# GSM_Status_LED_Driver.net
KiCad netlist of a schematic drawn in Altium Designer
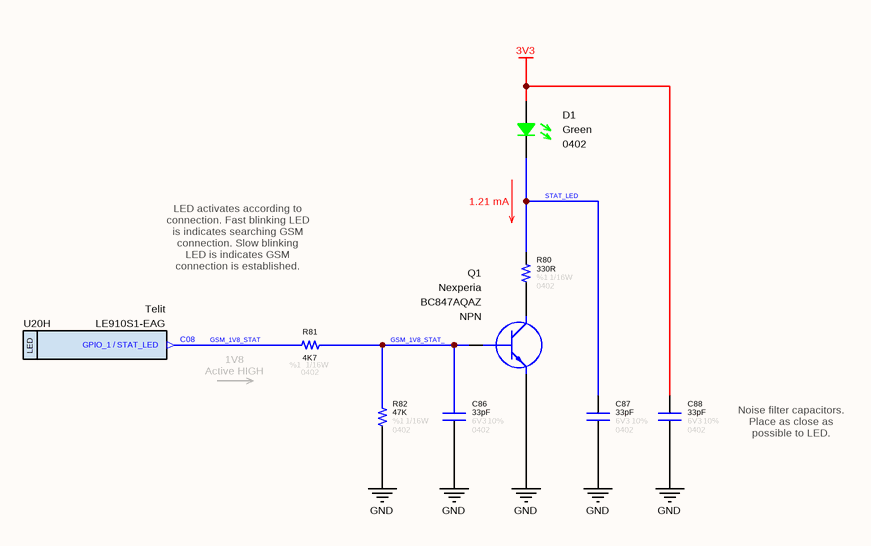
[diagram p0: GSM Status LED Driver.SchDoc]

(export (version "E")
  (design (tool "Eeschema 10.0.6"))
  (components
    (comp (ref "C86")
      (value "33pF")
      (footprint "CAPACITOR_0402")
      (description "Capacitor - 33pF [0402] (Ceramic)")
      (fields
        (field (name "MANUFACTURER PART NUMBER") "C0402C330J9RACAUTO")
        (field (name "TOLERANCE") "10%")
        (field (name "CASE") "0402")
        (field (name "VOLTAGE") "6V3")
      )
      (libsource (lib "Akkoyun") (part "Capacitor - 33pF [0402-6V3]"))
    )
    (comp (ref "C87")
      (value "33pF")
      (footprint "CAPACITOR_0402")
      (description "Capacitor - 33pF [0402] (Ceramic)")
      (fields
        (field (name "MANUFACTURER PART NUMBER") "C0402C330J9RACAUTO")
        (field (name "TOLERANCE") "10%")
        (field (name "CASE") "0402")
        (field (name "VOLTAGE") "6V3")
      )
      (libsource (lib "Akkoyun") (part "Capacitor - 33pF [0402-6V3]"))
    )
    (comp (ref "C88")
      (value "33pF")
      (footprint "CAPACITOR_0402")
      (description "Capacitor - 33pF [0402] (Ceramic)")
      (fields
        (field (name "MANUFACTURER PART NUMBER") "C0402C330J9RACAUTO")
        (field (name "TOLERANCE") "10%")
        (field (name "CASE") "0402")
        (field (name "VOLTAGE") "6V3")
      )
      (libsource (lib "Akkoyun") (part "Capacitor - 33pF [0402-6V3]"))
    )
    (comp (ref "D1")
      (value "SMD LED (Green)")
      (footprint "LED_0402")
      (description "Standard LEDs - SMD MINI-MOLD ULTRA COMPACT GREEN")
      (fields
        (field (name "MANUFACTURER PART NUMBER") "SML-P12MTT86R")
        (field (name "CASE") "0402")
        (field (name "COLOR") "Green")
      )
      (libsource (lib "Akkoyun") (part "Diode - LED (0402-Green)"))
    )
    (comp (ref "Q1")
      (value "BC847AQAZ")
      (footprint "SOT1215")
      (description "Bipolar NPN Transistors")
      (fields
        (field (name "MANUFACTURER NAME") "Nexperia")
        (field (name "MANUFACTURER PART NUMBER") "BC847AQAZ")
        (field (name "POLARITY") "NPN")
      )
      (libsource (lib "Akkoyun") (part "Transistor - BC847"))
    )
    (comp (ref "R80")
      (value "330R")
      (footprint "RESISTOR_0402")
      (description "Thick Film Resistors - SMD 1/16 W 330 Ohm 1%")
      (fields
        (field (name "MANUFACTURER PART NUMBER") "CRCW0402330RFKED")
        (field (name "CASE") "0402")
        (field (name "TOLERANCE") "%1")
        (field (name "POWER") "1/16W")
        (field (name "Comment") "330R - 0402 - %1 - 1/16W")
      )
      (libsource (lib "Akkoyun") (part "Resistor - 330R [0402]"))
    )
    (comp (ref "R81")
      (value "4K7")
      (footprint "RESISTOR_0402")
      (description "Thick Film Resistors - SMD 1/16 W 4.7 KOhm 1%")
      (fields
        (field (name "MANUFACTURER PART NUMBER") "CRCW04024K70FKED")
        (field (name "TOLERANCE") "%1")
        (field (name "CASE") "0402")
        (field (name "POWER") "1/16W")
        (field (name "Comment") "4K7 - 0402 - %1 - 1/16W")
      )
      (libsource (lib "Akkoyun") (part "Resistor - 4K7 [0402]"))
    )
    (comp (ref "R82")
      (value "47K")
      (footprint "RESISTOR_0402")
      (description "Thick Film Resistors - SMD 1/16 W 47 KOhm 1%")
      (fields
        (field (name "MANUFACTURER PART NUMBER") "CRCW040247K0FKED")
        (field (name "TOLERANCE") "%1")
        (field (name "CASE") "0402")
        (field (name "POWER") "1/16W")
        (field (name "Comment") "47K - 0402 - %1 - 1/16W")
      )
      (libsource (lib "Akkoyun") (part "Resistor - 47K [0402]"))
    )
    (comp (ref "U20")
      (value "LE910S1-EAG LTE GSM Module")
      (footprint "LE910 GSM Modem")
      (description "Telit LE910S1-EAG GPRS/GNSS Module")
      (fields
        (field (name "MANUFACTURER PART NUMBER") "LE910S1-EAG")
        (field (name "MANUFACTURER NAME") "Telit")
      )
      (libsource (lib "Akkoyun") (part "IC - LE910S1-EAG"))
    )
  )
  (nets
    (net (code "1") (name "/GSM_1V8_STAT") (class "Default")
      (node (ref "R81") (pin "2") (pinfunction "2_2") (pintype "passive"))
      (node (ref "U20") (pin "C08") (pinfunction "GPIO_1_/_STAT_LED_C08") (pintype "output"))
    )
    (net (code "2") (name "/GSM_1V8_STAT_") (class "Default")
      (node (ref "C86") (pin "2") (pinfunction "2_2") (pintype "passive"))
      (node (ref "Q1") (pin "1") (pinfunction "B_1") (pintype "passive"))
      (node (ref "R81") (pin "1") (pinfunction "1_1") (pintype "passive"))
      (node (ref "R82") (pin "2") (pinfunction "2_2") (pintype "passive"))
    )
    (net (code "3") (name "/STAT_LED") (class "Default")
      (node (ref "C87") (pin "2") (pinfunction "2_2") (pintype "passive"))
      (node (ref "D1") (pin "1") (pinfunction "1_1") (pintype "passive"))
      (node (ref "R80") (pin "2") (pinfunction "2_2") (pintype "passive"))
    )
    (net (code "4") (name "3V3") (class "Default")
      (node (ref "C88") (pin "2") (pinfunction "2_2") (pintype "passive"))
      (node (ref "D1") (pin "2") (pinfunction "2_2") (pintype "passive"))
    )
    (net (code "5") (name "GND") (class "Default")
      (node (ref "C86") (pin "1") (pinfunction "1_1") (pintype "passive"))
      (node (ref "C87") (pin "1") (pinfunction "1_1") (pintype "passive"))
      (node (ref "C88") (pin "1") (pinfunction "1_1") (pintype "passive"))
      (node (ref "Q1") (pin "2") (pinfunction "E_2") (pintype "passive"))
      (node (ref "R82") (pin "1") (pinfunction "1_1") (pintype "passive"))
    )
    (net (code "6") (name "Net-(Q1-C)") (class "Default")
      (node (ref "Q1") (pin "3") (pinfunction "C_3") (pintype "passive"))
      (node (ref "R80") (pin "1") (pinfunction "1_1") (pintype "passive"))
    )
  )
)
